# esp32_d1.net
KiCad netlist of a schematic drawn in Altium Designer
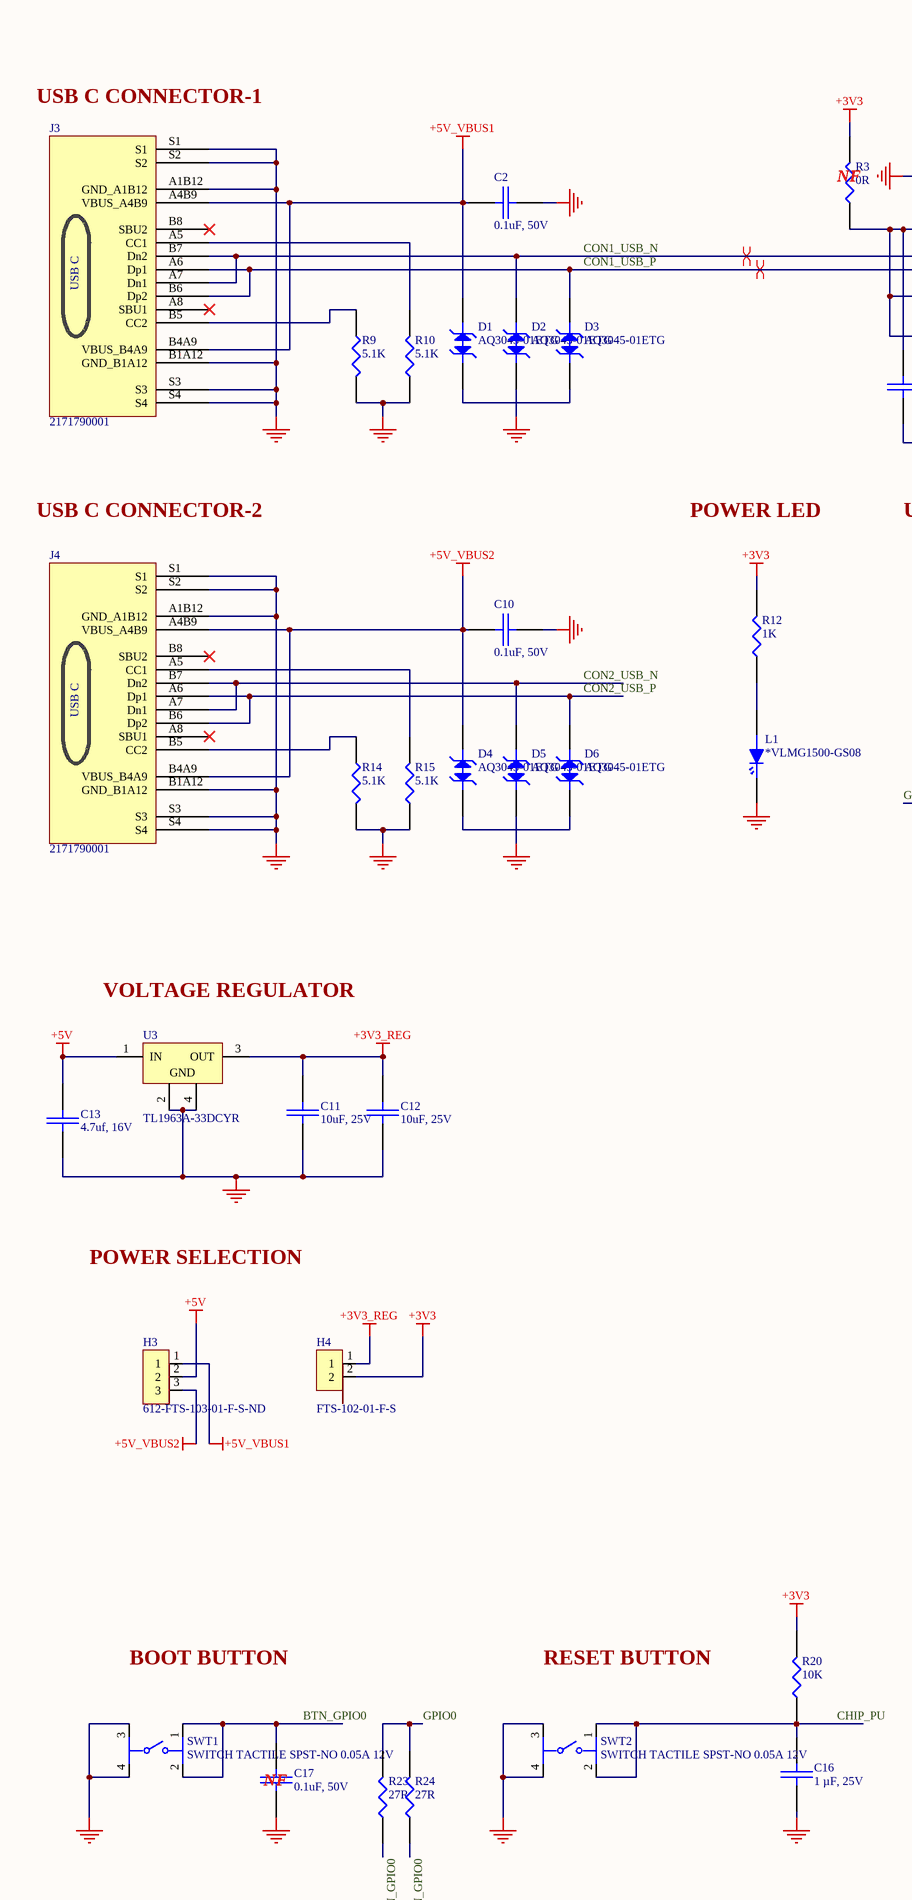
[diagram p0: esp32_d1.SchDoc, left]
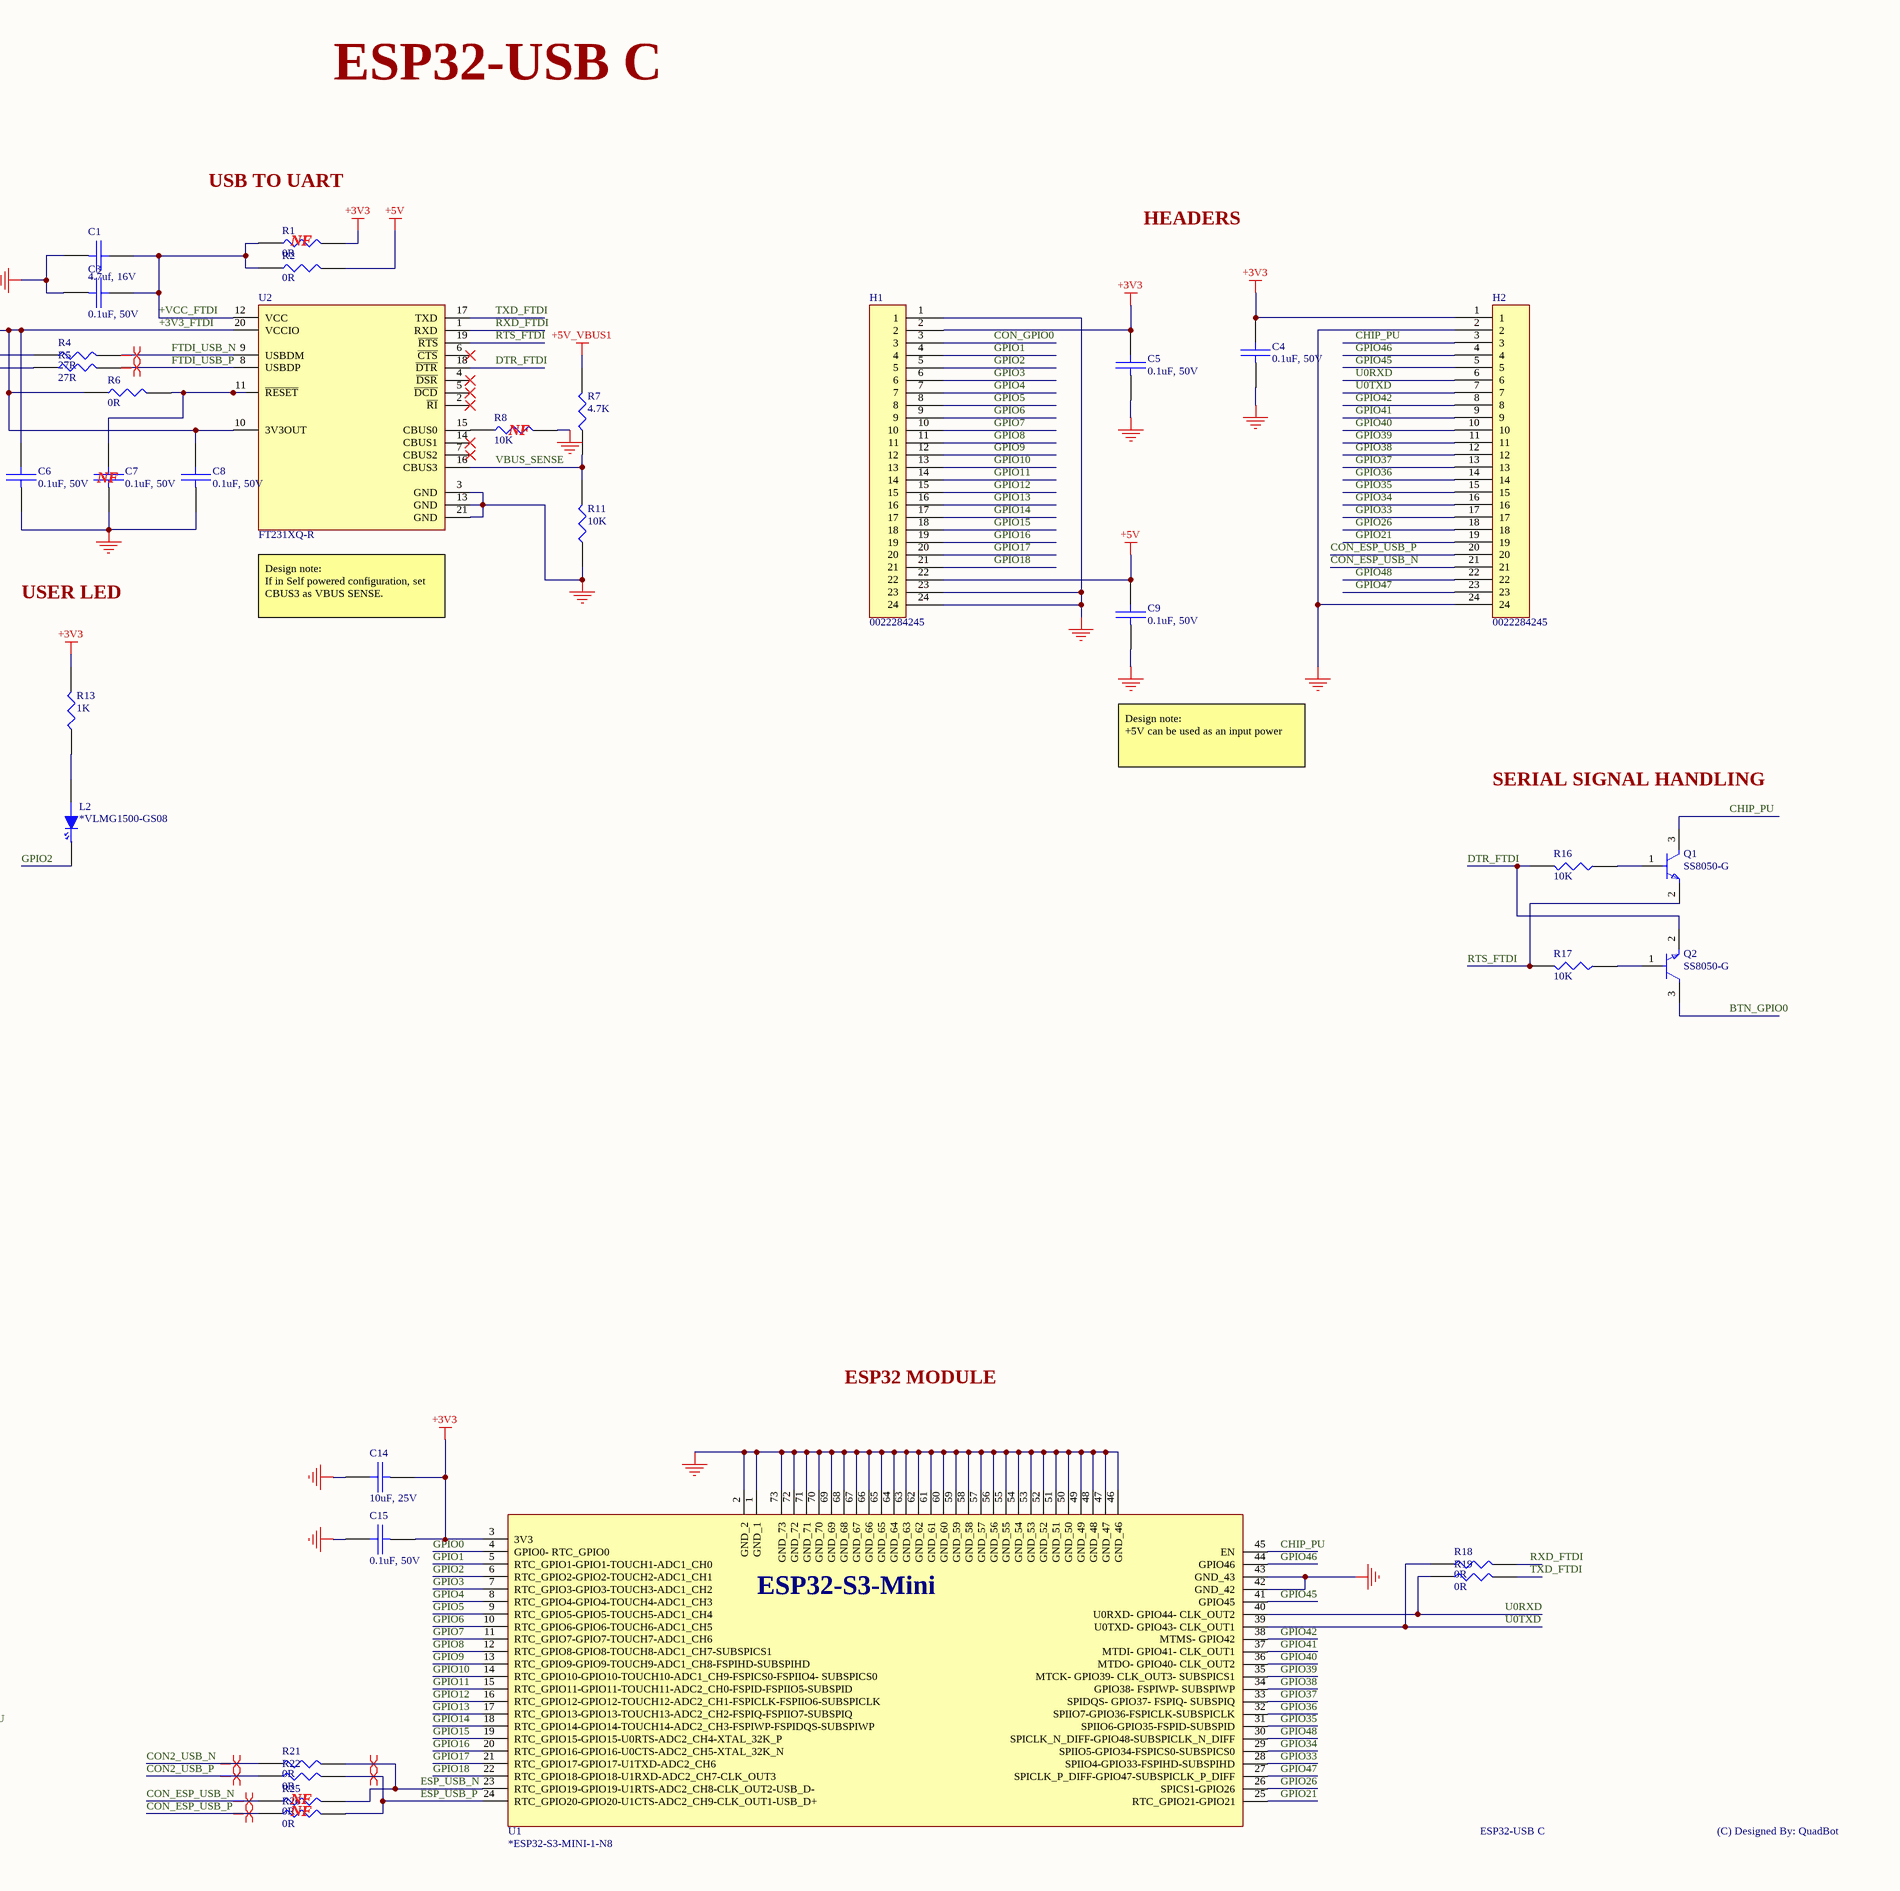
[diagram p1: esp32_d1.SchDoc, right]

(export (version "E")
  (design (tool "Eeschema 10.0.6"))
  (components
    (comp (ref "C1")
      (value "4.7uf, 16V")
      (footprint "CAPC1005X55N")
      (description "CAP CER 4.7UF 16V X5R 0402")
      (fields
        (field (name "MANUFACTURER") "Samsung")
        (field (name "MANUFACTURER PART NUMBER") "CL05A475MO5NUNC")
      )
      (libsource (lib "Esp32_Schlib1") (part "CL05A475MO5NUNC"))
    )
    (comp (ref "C2")
      (value "0.1uF, 50V")
      (footprint "CAPC1005X55N")
      (description "CAP CER 0.1UF 10V X7R 0402")
      (fields
        (field (name "MANUFACTURER") "Samsung")
        (field (name "MANUFACTURER PART NUMBER") "CL05B104KP5NNNC")
      )
      (libsource (lib "Esp32_Schlib1") (part "CL05B104KP5NNNC"))
    )
    (comp (ref "C3")
      (value "0.1uF, 50V")
      (footprint "CAPC1005X55N")
      (description "CAP CER 0.1UF 10V X7R 0402")
      (fields
        (field (name "MANUFACTURER") "Samsung")
        (field (name "MANUFACTURER PART NUMBER") "CL05B104KP5NNNC")
      )
      (libsource (lib "Esp32_Schlib1") (part "CL05B104KP5NNNC"))
    )
    (comp (ref "C4")
      (value "0.1uF, 50V")
      (footprint "CAPC1005X55N")
      (description "CAP CER 0.1UF 10V X7R 0402")
      (fields
        (field (name "MANUFACTURER") "Samsung")
        (field (name "MANUFACTURER PART NUMBER") "CL05B104KP5NNNC")
      )
      (libsource (lib "Esp32_Schlib1") (part "CL05B104KP5NNNC"))
    )
    (comp (ref "C5")
      (value "0.1uF, 50V")
      (footprint "CAPC1005X55N")
      (description "CAP CER 0.1UF 10V X7R 0402")
      (fields
        (field (name "MANUFACTURER") "Samsung")
        (field (name "MANUFACTURER PART NUMBER") "CL05B104KP5NNNC")
      )
      (libsource (lib "Esp32_Schlib1") (part "CL05B104KP5NNNC"))
    )
    (comp (ref "C6")
      (value "0.1uF, 50V")
      (footprint "CAPC1005X55N")
      (description "CAP CER 0.1UF 10V X7R 0402")
      (fields
        (field (name "MANUFACTURER") "Samsung")
        (field (name "MANUFACTURER PART NUMBER") "CL05B104KP5NNNC")
      )
      (libsource (lib "Esp32_Schlib1") (part "CL05B104KP5NNNC"))
    )
    (comp (ref "C7")
      (value "0.1uF, 50V")
      (footprint "CAPC1005X55N")
      (description "CAP CER 0.1UF 10V X7R 0402")
      (fields
        (field (name "MANUFACTURER") "Samsung")
        (field (name "MANUFACTURER PART NUMBER") "CL05B104KP5NNNC")
      )
      (libsource (lib "Esp32_Schlib1") (part "CL05B104KP5NNNC"))
    )
    (comp (ref "C8")
      (value "0.1uF, 50V")
      (footprint "CAPC1005X55N")
      (description "CAP CER 0.1UF 10V X7R 0402")
      (fields
        (field (name "MANUFACTURER") "Samsung")
        (field (name "MANUFACTURER PART NUMBER") "CL05B104KP5NNNC")
      )
      (libsource (lib "Esp32_Schlib1") (part "CL05B104KP5NNNC"))
    )
    (comp (ref "C9")
      (value "0.1uF, 50V")
      (footprint "CAPC1005X55N")
      (description "CAP CER 0.1UF 10V X7R 0402")
      (fields
        (field (name "MANUFACTURER") "Samsung")
        (field (name "MANUFACTURER PART NUMBER") "CL05B104KP5NNNC")
      )
      (libsource (lib "Esp32_Schlib1") (part "CL05B104KP5NNNC"))
    )
    (comp (ref "C10")
      (value "0.1uF, 50V")
      (footprint "CAPC1005X55N")
      (description "CAP CER 0.1UF 10V X7R 0402")
      (fields
        (field (name "MANUFACTURER") "Samsung")
        (field (name "MANUFACTURER PART NUMBER") "CL05B104KP5NNNC")
      )
      (libsource (lib "Esp32_Schlib1") (part "CL05B104KP5NNNC"))
    )
    (comp (ref "C11")
      (value "10uF, 25V")
      (footprint "CAPC1005X55N")
      (description "10V 10uF X5R ±20% 0402 Multilayer Ceramic Capacitors")
      (fields
        (field (name "MANUFACTURER") "Murata")
        (field (name "MANUFACTURER PART NUMBER") "GRM155R60J106ME15D")
      )
      (libsource (lib "Esp32_Schlib1") (part "GRM155R60J106ME15D"))
    )
    (comp (ref "C12")
      (value "10uF, 25V")
      (footprint "CAPC1005X55N")
      (description "10V 10uF X5R ±20% 0402 Multilayer Ceramic Capacitors")
      (fields
        (field (name "MANUFACTURER") "Murata")
        (field (name "MANUFACTURER PART NUMBER") "GRM155R60J106ME15D")
      )
      (libsource (lib "Esp32_Schlib1") (part "GRM155R60J106ME15D"))
    )
    (comp (ref "C13")
      (value "4.7uf, 16V")
      (footprint "CAPC1005X55N")
      (description "CAP CER 4.7UF 16V X5R 0402")
      (fields
        (field (name "MANUFACTURER") "Samsung")
        (field (name "MANUFACTURER PART NUMBER") "CL05A475MO5NUNC")
      )
      (libsource (lib "Esp32_Schlib1") (part "CL05A475MO5NUNC"))
    )
    (comp (ref "C14")
      (value "10uF, 25V")
      (footprint "CAPC1005X55N")
      (description "10V 10uF X5R ±20% 0402 Multilayer Ceramic Capacitors")
      (fields
        (field (name "MANUFACTURER") "Murata")
        (field (name "MANUFACTURER PART NUMBER") "GRM155R60J106ME15D")
      )
      (libsource (lib "Esp32_Schlib1") (part "GRM155R60J106ME15D"))
    )
    (comp (ref "C15")
      (value "0.1uF, 50V")
      (footprint "CAPC1005X55N")
      (description "CAP CER 0.1UF 10V X7R 0402")
      (fields
        (field (name "MANUFACTURER") "Samsung")
        (field (name "MANUFACTURER PART NUMBER") "CL05B104KP5NNNC")
      )
      (libsource (lib "Esp32_Schlib1") (part "CL05B104KP5NNNC"))
    )
    (comp (ref "C16")
      (value "1 µF, 25V")
      (footprint "CAPC1005X55N")
      (description "1 µF ±10% 25V")
      (fields
        (field (name "MANUFACTURER") "Samsung")
        (field (name "MANUFACTURER PART NUMBER") "CL05A105KA5NQNC")
      )
      (libsource (lib "Esp32_Schlib1") (part "CL05A105KA5NQNC"))
    )
    (comp (ref "C17")
      (value "0.1uF, 50V")
      (footprint "CAPC1005X55N")
      (description "CAP CER 0.1UF 10V X7R 0402")
      (fields
        (field (name "MANUFACTURER") "Samsung")
        (field (name "MANUFACTURER PART NUMBER") "CL05B104KP5NNNC")
      )
      (libsource (lib "Esp32_Schlib1") (part "CL05B104KP5NNNC"))
    )
    (comp (ref "D1")
      (value "AQ3045-01ETG")
      (footprint "SOD882")
      (description "Trans Voltage Suppressor Diode, 40W, 5.3V V(RWM), Bidirectional, 1 Element, Silicon, MO-236")
      (fields (field (name "MANUFACTURER") "Littelfuse") (field (name "LCSC PART NUMBER") "C3710326"))
      (libsource (lib "Esp32_Schlib1") (part "AQ3045-01ETG"))
    )
    (comp (ref "D2")
      (value "AQ3045-01ETG")
      (footprint "SOD882")
      (description "Trans Voltage Suppressor Diode, 40W, 5.3V V(RWM), Bidirectional, 1 Element, Silicon, MO-236")
      (fields (field (name "MANUFACTURER") "Littelfuse") (field (name "LCSC PART NUMBER") "C3710326"))
      (libsource (lib "Esp32_Schlib1") (part "AQ3045-01ETG"))
    )
    (comp (ref "D3")
      (value "AQ3045-01ETG")
      (footprint "SOD882")
      (description "Trans Voltage Suppressor Diode, 40W, 5.3V V(RWM), Bidirectional, 1 Element, Silicon, MO-236")
      (fields (field (name "MANUFACTURER") "Littelfuse") (field (name "LCSC PART NUMBER") "C3710326"))
      (libsource (lib "Esp32_Schlib1") (part "AQ3045-01ETG"))
    )
    (comp (ref "D4")
      (value "AQ3045-01ETG")
      (footprint "SOD882")
      (description "Trans Voltage Suppressor Diode, 40W, 5.3V V(RWM), Bidirectional, 1 Element, Silicon, MO-236")
      (fields (field (name "MANUFACTURER") "Littelfuse") (field (name "LCSC PART NUMBER") "C3710326"))
      (libsource (lib "Esp32_Schlib1") (part "AQ3045-01ETG"))
    )
    (comp (ref "D5")
      (value "AQ3045-01ETG")
      (footprint "SOD882")
      (description "Trans Voltage Suppressor Diode, 40W, 5.3V V(RWM), Bidirectional, 1 Element, Silicon, MO-236")
      (fields (field (name "MANUFACTURER") "Littelfuse") (field (name "LCSC PART NUMBER") "C3710326"))
      (libsource (lib "Esp32_Schlib1") (part "AQ3045-01ETG"))
    )
    (comp (ref "D6")
      (value "AQ3045-01ETG")
      (footprint "SOD882")
      (description "Trans Voltage Suppressor Diode, 40W, 5.3V V(RWM), Bidirectional, 1 Element, Silicon, MO-236")
      (fields (field (name "MANUFACTURER") "Littelfuse") (field (name "LCSC PART NUMBER") "C3710326"))
      (libsource (lib "Esp32_Schlib1") (part "AQ3045-01ETG"))
    )
    (comp (ref "H1")
      (value "0022284245")
      (footprint "HDR_1X24_2.54MM")
      (description "CONN HEADER VERT 24POS 2.54MM")
      (fields (field (name "MANUFACTURER") "Molex") (field (name "LCSC PART NUMBER") "C7145888"))
      (libsource (lib "") (part "0022284245_1"))
    )
    (comp (ref "H2")
      (value "0022284245")
      (footprint "HDR_1X24_2.54MM")
      (description "CONN HEADER VERT 24POS 2.54MM")
      (fields (field (name "MANUFACTURER") "Molex") (field (name "LCSC PART NUMBER") "C7145888"))
      (libsource (lib "Esp32_Schlib1") (part "0022284245"))
    )
    (comp (ref "H3")
      (value "612-FTS-103-01-F-S-ND")
      (footprint "HDR_1X3_2.54MM")
      (description "Board Connector, 3 Contact(s), 1 Row(s), Male, Straight, Solder Terminal")
      (fields
        (field (name "MANUFACTURER") "Samtec")
        (field (name "MANUFACTURER PART NUMBER") "FTS-103-01-F-S")
      )
      (libsource (lib "Esp32_Schlib1") (part "FTS-103-01-F-S"))
    )
    (comp (ref "H4")
      (value "FTS-102-01-F-S")
      (footprint "HDR_1X2_2.54MM")
      (fields (field (name "MANUFACTURER") "Samtec") (field (name "LCSC PART NUMBER") "C6045317"))
      (libsource (lib "Esp32_Schlib1") (part "FTS-102-01-F-S"))
    )
    (comp (ref "J3")
      (value "2171790001")
      (footprint "FP-2171790001-MFG")
      (description "CONN RCP USB2.0 TYP C 24P SMD RA")
      (fields (field (name "MANUFACTURER") "Molex") (field (name "MANUFACTURER PART NUMBER") "217179-0001"))
      (libsource (lib "Esp32_Schlib1") (part "217179-0001"))
    )
    (comp (ref "J4")
      (value "2171790001")
      (footprint "FP-2171790001-MFG")
      (description "CONN RCP USB2.0 TYP C 24P SMD RA")
      (fields (field (name "MANUFACTURER") "Molex") (field (name "MANUFACTURER PART NUMBER") "217179-0001"))
      (libsource (lib "Esp32_Schlib1") (part "217179-0001"))
    )
    (comp (ref "L1")
      (value "*VLMG1500-GS08")
      (footprint "LEDC1005X35N")
      (description "LED YLW-GRN 0402 SMD")
      (fields
        (field (name "MANUFACTURER") "Vishay")
        (field (name "MANUFACTURER PART NUMBER") "VLMG1500-GS08")
      )
      (libsource (lib "Esp32_Schlib1") (part "VLMG1500-GS08"))
    )
    (comp (ref "L2")
      (value "*VLMG1500-GS08")
      (footprint "LEDC1005X35N")
      (description "LED YLW-GRN 0402 SMD")
      (fields
        (field (name "MANUFACTURER") "Vishay")
        (field (name "MANUFACTURER PART NUMBER") "VLMG1500-GS08")
      )
      (libsource (lib "Esp32_Schlib1") (part "VLMG1500-GS08"))
    )
    (comp (ref "Q1")
      (value "SS8050-G")
      (footprint "FP-SS8050-G-IPC_B")
      (description "TRANS NPN 25V 1.5A SOT23-3")
      (fields (field (name "MANUFACTURER") "Comchip"))
      (libsource (lib "Esp32_Schlib1") (part "SS8050-G"))
    )
    (comp (ref "Q2")
      (value "SS8050-G")
      (footprint "FP-SS8050-G-IPC_B")
      (description "TRANS NPN 25V 1.5A SOT23-3")
      (fields (field (name "MANUFACTURER") "Comchip"))
      (libsource (lib "Esp32_Schlib1") (part "SS8050-G"))
    )
    (comp (ref "R1")
      (value "0R")
      (footprint "RESC1005X40N")
      (description "RES 0 OHM JUMPER 1/16W 0402")
      (fields
        (field (name "MANUFACTURER") "Yageo")
        (field (name "MANUFACTURER PART NUMBER") "RC0402JR-070RL")
      )
      (libsource (lib "Esp32_Schlib1") (part "RC0402JR-070RL"))
    )
    (comp (ref "R2")
      (value "0R")
      (footprint "RESC1005X40N")
      (description "RES 0 OHM JUMPER 1/16W 0402")
      (fields
        (field (name "MANUFACTURER") "Yageo")
        (field (name "MANUFACTURER PART NUMBER") "RC0402JR-070RL")
      )
      (libsource (lib "Esp32_Schlib1") (part "RC0402JR-070RL"))
    )
    (comp (ref "R3")
      (value "0R")
      (footprint "RESC1005X40N")
      (description "RES 0 OHM JUMPER 1/16W 0402")
      (fields
        (field (name "MANUFACTURER") "Yageo")
        (field (name "MANUFACTURER PART NUMBER") "RC0402JR-070RL")
      )
      (libsource (lib "Esp32_Schlib1") (part "RC0402JR-070RL"))
    )
    (comp (ref "R4")
      (value "27R")
      (footprint "RESC1005X40N")
      (description "RES 27 OHM 5% 1/16W 0402")
      (fields
        (field (name "MANUFACTURER") "Yageo")
        (field (name "MANUFACTURER PART NUMBER") "RC0402JR-0727RL")
      )
      (libsource (lib "Esp32_Schlib1") (part "RC0402JR-0727RL"))
    )
    (comp (ref "R5")
      (value "27R")
      (footprint "RESC1005X40N")
      (description "RES 27 OHM 5% 1/16W 0402")
      (fields
        (field (name "MANUFACTURER") "Yageo")
        (field (name "MANUFACTURER PART NUMBER") "RC0402JR-0727RL")
      )
      (libsource (lib "Esp32_Schlib1") (part "RC0402JR-0727RL"))
    )
    (comp (ref "R6")
      (value "0R")
      (footprint "RESC1005X40N")
      (description "RES 0 OHM JUMPER 1/16W 0402")
      (fields
        (field (name "MANUFACTURER") "Yageo")
        (field (name "MANUFACTURER PART NUMBER") "RC0402JR-070RL")
      )
      (libsource (lib "Esp32_Schlib1") (part "RC0402JR-070RL"))
    )
    (comp (ref "R7")
      (value "4.7K")
      (footprint "RESC1005X40N")
      (description "RES 4.7K OHM 1% 1/16W 0402")
      (fields
        (field (name "MANUFACTURER") "Yageo")
        (field (name "MANUFACTURER PART NUMBER") "RC0402FR-074K7L")
      )
      (libsource (lib "Esp32_Schlib1") (part "RC0402FR-074K7L"))
    )
    (comp (ref "R8")
      (value "10K")
      (footprint "RESC1005X40N")
      (description "10 kOhms ±1% 0.063W, 1/16W")
      (fields
        (field (name "MANUFACTURER") "Samsung")
        (field (name "MANUFACTURER PART NUMBER") "RC1005F103CS")
      )
      (libsource (lib "Esp32_Schlib1") (part "RC1005F103CS"))
    )
    (comp (ref "R9")
      (value "5.1K")
      (footprint "RESC1005X40N")
      (description "RES 5.1K OHM 1% 1/16W 0402")
      (fields
        (field (name "MANUFACTURER") "Yageo")
        (field (name "MANUFACTURER PART NUMBER") "RC0402FR-075K1L")
      )
      (libsource (lib "Esp32_Schlib1") (part "RC0402FR-075K1L"))
    )
    (comp (ref "R10")
      (value "5.1K")
      (footprint "RESC1005X40N")
      (description "RES 5.1K OHM 1% 1/16W 0402")
      (fields
        (field (name "MANUFACTURER") "Yageo")
        (field (name "MANUFACTURER PART NUMBER") "RC0402FR-075K1L")
      )
      (libsource (lib "Esp32_Schlib1") (part "RC0402FR-075K1L"))
    )
    (comp (ref "R11")
      (value "10K")
      (footprint "RESC1005X40N")
      (description "10 kOhms ±1% 0.063W, 1/16W")
      (fields
        (field (name "MANUFACTURER") "Samsung")
        (field (name "MANUFACTURER PART NUMBER") "RC1005F103CS")
      )
      (libsource (lib "Esp32_Schlib1") (part "RC1005F103CS"))
    )
    (comp (ref "R12")
      (value "1K")
      (footprint "RESC1005X40N")
      (description "RES 1K OHM 1% 1/16W 0402")
      (fields
        (field (name "MANUFACTURER") "Yageo")
        (field (name "MANUFACTURER PART NUMBER") "RC0402FR-071KL")
      )
      (libsource (lib "Esp32_Schlib1") (part "RC0402FR-071KL"))
    )
    (comp (ref "R13")
      (value "1K")
      (footprint "RESC1005X40N")
      (description "RES 1K OHM 1% 1/16W 0402")
      (fields
        (field (name "MANUFACTURER") "Yageo")
        (field (name "MANUFACTURER PART NUMBER") "RC0402FR-071KL")
      )
      (libsource (lib "Esp32_Schlib1") (part "RC0402FR-071KL"))
    )
    (comp (ref "R14")
      (value "5.1K")
      (footprint "RESC1005X40N")
      (description "RES 5.1K OHM 1% 1/16W 0402")
      (fields
        (field (name "MANUFACTURER") "Yageo")
        (field (name "MANUFACTURER PART NUMBER") "RC0402FR-075K1L")
      )
      (libsource (lib "Esp32_Schlib1") (part "RC0402FR-075K1L"))
    )
    (comp (ref "R15")
      (value "5.1K")
      (footprint "RESC1005X40N")
      (description "RES 5.1K OHM 1% 1/16W 0402")
      (fields
        (field (name "MANUFACTURER") "Yageo")
        (field (name "MANUFACTURER PART NUMBER") "RC0402FR-075K1L")
      )
      (libsource (lib "Esp32_Schlib1") (part "RC0402FR-075K1L"))
    )
    (comp (ref "R16")
      (value "10K")
      (footprint "RESC1005X40N")
      (description "10 kOhms ±1% 0.063W, 1/16W")
      (fields
        (field (name "MANUFACTURER") "Samsung")
        (field (name "MANUFACTURER PART NUMBER") "RC1005F103CS")
      )
      (libsource (lib "Esp32_Schlib1") (part "RC1005F103CS"))
    )
    (comp (ref "R17")
      (value "10K")
      (footprint "RESC1005X40N")
      (description "10 kOhms ±1% 0.063W, 1/16W")
      (fields
        (field (name "MANUFACTURER") "Samsung")
        (field (name "MANUFACTURER PART NUMBER") "RC1005F103CS")
      )
      (libsource (lib "Esp32_Schlib1") (part "RC1005F103CS"))
    )
    (comp (ref "R18")
      (value "0R")
      (footprint "RESC1005X40N")
      (description "RES 0 OHM JUMPER 1/16W 0402")
      (fields
        (field (name "MANUFACTURER") "Yageo")
        (field (name "MANUFACTURER PART NUMBER") "RC0402JR-070RL")
      )
      (libsource (lib "Esp32_Schlib1") (part "RC0402JR-070RL"))
    )
    (comp (ref "R19")
      (value "0R")
      (footprint "RESC1005X40N")
      (description "RES 0 OHM JUMPER 1/16W 0402")
      (fields
        (field (name "MANUFACTURER") "Yageo")
        (field (name "MANUFACTURER PART NUMBER") "RC0402JR-070RL")
      )
      (libsource (lib "Esp32_Schlib1") (part "RC0402JR-070RL"))
    )
    (comp (ref "R20")
      (value "10K")
      (footprint "RESC1005X40N")
      (description "10 kOhms ±1% 0.063W, 1/16W")
      (fields
        (field (name "MANUFACTURER") "Samsung")
        (field (name "MANUFACTURER PART NUMBER") "RC1005F103CS")
      )
      (libsource (lib "Esp32_Schlib1") (part "RC1005F103CS"))
    )
    (comp (ref "R21")
      (value "0R")
      (footprint "RESC1005X40N")
      (description "RES 0 OHM JUMPER 1/16W 0402")
      (fields
        (field (name "MANUFACTURER") "Yageo")
        (field (name "MANUFACTURER PART NUMBER") "RC0402JR-070RL")
      )
      (libsource (lib "Esp32_Schlib1") (part "RC0402JR-070RL"))
    )
    (comp (ref "R22")
      (value "0R")
      (footprint "RESC1005X40N")
      (description "RES 0 OHM JUMPER 1/16W 0402")
      (fields
        (field (name "MANUFACTURER") "Yageo")
        (field (name "MANUFACTURER PART NUMBER") "RC0402JR-070RL")
      )
      (libsource (lib "Esp32_Schlib1") (part "RC0402JR-070RL"))
    )
    (comp (ref "R23")
      (value "27R")
      (footprint "RESC1005X40N")
      (description "RES 27 OHM 5% 1/16W 0402")
      (fields
        (field (name "MANUFACTURER") "Yageo")
        (field (name "MANUFACTURER PART NUMBER") "RC0402JR-0727RL")
      )
      (libsource (lib "Esp32_Schlib1") (part "RC0402JR-0727RL"))
    )
    (comp (ref "R24")
      (value "27R")
      (footprint "RESC1005X40N")
      (description "RES 27 OHM 5% 1/16W 0402")
      (fields
        (field (name "MANUFACTURER") "Yageo")
        (field (name "MANUFACTURER PART NUMBER") "RC0402JR-0727RL")
      )
      (libsource (lib "Esp32_Schlib1") (part "RC0402JR-0727RL"))
    )
    (comp (ref "R25")
      (value "0R")
      (footprint "RESC1005X40N")
      (description "RES 0 OHM JUMPER 1/16W 0402")
      (fields
        (field (name "MANUFACTURER") "Yageo")
        (field (name "MANUFACTURER PART NUMBER") "RC0402JR-070RL")
      )
      (libsource (lib "Esp32_Schlib1") (part "RC0402JR-070RL"))
    )
    (comp (ref "R26")
      (value "0R")
      (footprint "RESC1005X40N")
      (description "RES 0 OHM JUMPER 1/16W 0402")
      (fields
        (field (name "MANUFACTURER") "Yageo")
        (field (name "MANUFACTURER PART NUMBER") "RC0402JR-070RL")
      )
      (libsource (lib "Esp32_Schlib1") (part "RC0402JR-070RL"))
    )
    (comp (ref "SWT1")
      (value "SWITCH TACTILE SPST-NO 0.05A 12V")
      (footprint "FP-PTS645SH50SMTR92LFS-MFG")
      (fields
        (field (name "MANUFACTURER") "ITT C&K")
        (field (name "MANUFACTURER PART NUMBER") "PTS645SH50SMTR92LFS")
        (field (name "LCSC PART NUMBER") "C221869")
      )
      (libsource (lib "Esp32_Schlib1") (part "PTS645SH50SMTR92LFS"))
    )
    (comp (ref "SWT2")
      (value "SWITCH TACTILE SPST-NO 0.05A 12V")
      (footprint "FP-PTS645SH50SMTR92LFS-MFG")
      (fields
        (field (name "MANUFACTURER") "ITT C&K")
        (field (name "MANUFACTURER PART NUMBER") "PTS645SH50SMTR92LFS")
        (field (name "LCSC PART NUMBER") "C221869")
      )
      (libsource (lib "Esp32_Schlib1") (part "PTS645SH50SMTR92LFS"))
    )
    (comp (ref "U1")
      (value "*ESP32-S3-MINI-1-N8")
      (footprint "XCVR_ESP32-S3-MINI-1-N8")
      (description "SMD module, ESP32-S3FN8, 8 MB SPI flash, PCB antenna")
      (fields
        (field (name "MANUFACTURER") "Espressif Systems")
        (field (name "MANUFACTURER PART NUMBER") "ESP32-S3-MINI-1-N8")
      )
      (libsource (lib "Esp32_Schlib1") (part "ESP32-S3-MINI-1-N8"))
    )
    (comp (ref "U2")
      (value "FT231XQ-R")
      (footprint "FP-QFN-20-IPC_B")
      (description "IC USB SERIAL FULL UART 20QFN")
      (fields (field (name "MANUFACTURER") "FTDI") (field (name "LCSC PART NUMBER") "C132159"))
      (libsource (lib "Esp32_Schlib1") (part "FT231XQ-R"))
    )
    (comp (ref "U3")
      (value "TL1963A-33DCYR")
      (footprint "DCY0004A_N")
      (description "IC REG LINEAR 3.3V 1.5A SOT223-4")
      (fields (field (name "MANUFACTURER") "Texas Instruments") (field (name "LCSC PART NUMBER") "C181262"))
      (libsource (lib "Esp32_Schlib1") (part "TL1963A-33DCYR"))
    )
  )
  (nets
    (net (code "1") (name "+3V3") (class "Default")
      (node (ref "C14") (pin "2") (pinfunction "2_2") (pintype "passive"))
      (node (ref "C15") (pin "2") (pinfunction "2_2") (pintype "passive"))
      (node (ref "C4") (pin "1") (pinfunction "1_1") (pintype "passive"))
      (node (ref "C5") (pin "1") (pinfunction "1_1") (pintype "passive"))
      (node (ref "H1") (pin "2") (pinfunction "2_2") (pintype "passive"))
      (node (ref "H2") (pin "1") (pinfunction "1_1") (pintype "passive"))
      (node (ref "H4") (pin "2") (pinfunction "2_2") (pintype "passive"))
      (node (ref "R1") (pin "2") (pinfunction "2_2") (pintype "passive"))
      (node (ref "R12") (pin "2") (pinfunction "2_2") (pintype "passive"))
      (node (ref "R13") (pin "2") (pinfunction "2_2") (pintype "passive"))
      (node (ref "R20") (pin "2") (pinfunction "2_2") (pintype "passive"))
      (node (ref "R3") (pin "2") (pinfunction "2_2") (pintype "passive"))
      (node (ref "U1") (pin "3") (pinfunction "3V3_3") (pintype "passive"))
    )
    (net (code "2") (name "+3V3_REG") (class "Default")
      (node (ref "C11") (pin "2") (pinfunction "2_2") (pintype "passive"))
      (node (ref "C12") (pin "2") (pinfunction "2_2") (pintype "passive"))
      (node (ref "H4") (pin "1") (pinfunction "1_1") (pintype "passive"))
      (node (ref "U3") (pin "3") (pinfunction "OUT_3") (pintype "power_in"))
    )
    (net (code "3") (name "+5V") (class "Default")
      (node (ref "C13") (pin "1") (pinfunction "1_1") (pintype "passive"))
      (node (ref "C9") (pin "1") (pinfunction "1_1") (pintype "passive"))
      (node (ref "H1") (pin "22") (pinfunction "22_22") (pintype "passive"))
      (node (ref "H3") (pin "2") (pinfunction "2_2") (pintype "passive"))
      (node (ref "R2") (pin "2") (pinfunction "2_2") (pintype "passive"))
      (node (ref "U3") (pin "1") (pinfunction "IN_1") (pintype "power_in"))
    )
    (net (code "4") (name "+5V_VBUS1") (class "Default")
      (node (ref "C2") (pin "2") (pinfunction "2_2") (pintype "passive"))
      (node (ref "D1") (pin "1") (pinfunction "1_1") (pintype "passive"))
      (node (ref "H3") (pin "1") (pinfunction "1_1") (pintype "passive"))
      (node (ref "J3") (pin "A4B9") (pinfunction "VBUS_A4B9_A4B9") (pintype "passive"))
      (node (ref "J3") (pin "B4A9") (pinfunction "VBUS_B4A9_B4A9") (pintype "passive"))
      (node (ref "R7") (pin "2") (pinfunction "2_2") (pintype "passive"))
    )
    (net (code "5") (name "+5V_VBUS2") (class "Default")
      (node (ref "C10") (pin "2") (pinfunction "2_2") (pintype "passive"))
      (node (ref "D4") (pin "1") (pinfunction "1_1") (pintype "passive"))
      (node (ref "H3") (pin "3") (pinfunction "3_3") (pintype "passive"))
      (node (ref "J4") (pin "A4B9") (pinfunction "VBUS_A4B9_A4B9") (pintype "passive"))
      (node (ref "J4") (pin "B4A9") (pinfunction "VBUS_B4A9_B4A9") (pintype "passive"))
    )
    (net (code "6") (name "/+3V3_FTDI") (class "Default")
      (node (ref "C6") (pin "1") (pinfunction "1_1") (pintype "passive"))
      (node (ref "C8") (pin "1") (pinfunction "1_1") (pintype "passive"))
      (node (ref "R3") (pin "1") (pinfunction "1_1") (pintype "passive"))
      (node (ref "R6") (pin "1") (pinfunction "1_1") (pintype "passive"))
      (node (ref "U2") (pin "10") (pinfunction "3V3OUT_10") (pintype "passive"))
      (node (ref "U2") (pin "20") (pinfunction "VCCIO_20") (pintype "passive"))
    )
    (net (code "7") (name "/+VCC_FTDI") (class "Default")
      (node (ref "C1") (pin "1") (pinfunction "1_1") (pintype "passive"))
      (node (ref "C3") (pin "1") (pinfunction "1_1") (pintype "passive"))
      (node (ref "R1") (pin "1") (pinfunction "1_1") (pintype "passive"))
      (node (ref "R2") (pin "1") (pinfunction "1_1") (pintype "passive"))
      (node (ref "U2") (pin "12") (pinfunction "VCC_12") (pintype "passive"))
    )
    (net (code "8") (name "/BTN_GPIO0") (class "Default")
      (node (ref "C17") (pin "2") (pinfunction "2_2") (pintype "passive"))
      (node (ref "Q2") (pin "3") (pinfunction "C_3") (pintype "passive"))
      (node (ref "R24") (pin "1") (pinfunction "1_1") (pintype "passive"))
      (node (ref "SWT1") (pin "1") (pinfunction "1_1") (pintype "passive"))
      (node (ref "SWT1") (pin "2") (pinfunction "2_2") (pintype "passive"))
    )
    (net (code "9") (name "/CHIP_PU") (class "Default")
      (node (ref "C16") (pin "1") (pinfunction "1_1") (pintype "passive"))
      (node (ref "H2") (pin "3") (pinfunction "3_3") (pintype "passive"))
      (node (ref "Q1") (pin "3") (pinfunction "C_3") (pintype "passive"))
      (node (ref "R20") (pin "1") (pinfunction "1_1") (pintype "passive"))
      (node (ref "SWT2") (pin "1") (pinfunction "1_1") (pintype "passive"))
      (node (ref "SWT2") (pin "2") (pinfunction "2_2") (pintype "passive"))
      (node (ref "U1") (pin "45") (pinfunction "EN_45") (pintype "passive"))
    )
    (net (code "10") (name "/CON1_USB_N") (class "Default")
      (node (ref "D2") (pin "1") (pinfunction "1_1") (pintype "passive"))
      (node (ref "J3") (pin "A7") (pinfunction "Dn1_A7") (pintype "passive"))
      (node (ref "J3") (pin "B7") (pinfunction "Dn2_B7") (pintype "passive"))
      (node (ref "R4") (pin "1") (pinfunction "1_1") (pintype "passive"))
    )
    (net (code "11") (name "/CON1_USB_P") (class "Default")
      (node (ref "D3") (pin "1") (pinfunction "1_1") (pintype "passive"))
      (node (ref "J3") (pin "A6") (pinfunction "Dp1_A6") (pintype "passive"))
      (node (ref "J3") (pin "B6") (pinfunction "Dp2_B6") (pintype "passive"))
      (node (ref "R5") (pin "1") (pinfunction "1_1") (pintype "passive"))
    )
    (net (code "12") (name "/CON2_USB_N") (class "Default")
      (node (ref "D5") (pin "1") (pinfunction "1_1") (pintype "passive"))
      (node (ref "J4") (pin "A7") (pinfunction "Dn1_A7") (pintype "passive"))
      (node (ref "J4") (pin "B7") (pinfunction "Dn2_B7") (pintype "passive"))
      (node (ref "R21") (pin "1") (pinfunction "1_1") (pintype "passive"))
    )
    (net (code "13") (name "/CON2_USB_P") (class "Default")
      (node (ref "D6") (pin "1") (pinfunction "1_1") (pintype "passive"))
      (node (ref "J4") (pin "A6") (pinfunction "Dp1_A6") (pintype "passive"))
      (node (ref "J4") (pin "B6") (pinfunction "Dp2_B6") (pintype "passive"))
      (node (ref "R22") (pin "1") (pinfunction "1_1") (pintype "passive"))
    )
    (net (code "14") (name "/CON_ESP_USB_N") (class "Default")
      (node (ref "H2") (pin "21") (pinfunction "21_21") (pintype "passive"))
      (node (ref "R25") (pin "1") (pinfunction "1_1") (pintype "passive"))
    )
    (net (code "15") (name "/CON_ESP_USB_P") (class "Default")
      (node (ref "H2") (pin "20") (pinfunction "20_20") (pintype "passive"))
      (node (ref "R26") (pin "1") (pinfunction "1_1") (pintype "passive"))
    )
    (net (code "16") (name "/CON_GPIO0") (class "Default")
      (node (ref "H1") (pin "3") (pinfunction "3_3") (pintype "passive"))
      (node (ref "R23") (pin "1") (pinfunction "1_1") (pintype "passive"))
    )
    (net (code "17") (name "/DTR_FTDI") (class "Default")
      (node (ref "Q2") (pin "2") (pinfunction "E_2") (pintype "passive"))
      (node (ref "R16") (pin "2") (pinfunction "2_2") (pintype "passive"))
      (node (ref "U2") (pin "18") (pinfunction "~{DTR}_18") (pintype "passive"))
    )
    (net (code "18") (name "/ESP_USB_N") (class "Default")
      (node (ref "R21") (pin "2") (pinfunction "2_2") (pintype "passive"))
      (node (ref "R25") (pin "2") (pinfunction "2_2") (pintype "passive"))
      (node (ref "U1") (pin "23") (pinfunction "RTC_GPIO19-GPIO19-U1RTS-ADC2_CH8-CLK_OUT2-USB_D-_23") (pintype "passive"))
    )
    (net (code "19") (name "/ESP_USB_P") (class "Default")
      (node (ref "R22") (pin "2") (pinfunction "2_2") (pintype "passive"))
      (node (ref "R26") (pin "2") (pinfunction "2_2") (pintype "passive"))
      (node (ref "U1") (pin "24") (pinfunction "RTC_GPIO20-GPIO20-U1CTS-ADC2_CH9-CLK_OUT1-USB_D+_24") (pintype "passive"))
    )
    (net (code "20") (name "/FTDI_USB_N") (class "Default")
      (node (ref "R4") (pin "2") (pinfunction "2_2") (pintype "passive"))
      (node (ref "U2") (pin "9") (pinfunction "USBDM_9") (pintype "passive"))
    )
    (net (code "21") (name "/FTDI_USB_P") (class "Default")
      (node (ref "R5") (pin "2") (pinfunction "2_2") (pintype "passive"))
      (node (ref "U2") (pin "8") (pinfunction "USBDP_8") (pintype "passive"))
    )
    (net (code "22") (name "/GPIO0") (class "Default")
      (node (ref "R23") (pin "2") (pinfunction "2_2") (pintype "passive"))
      (node (ref "R24") (pin "2") (pinfunction "2_2") (pintype "passive"))
      (node (ref "U1") (pin "4") (pinfunction "GPIO0-_RTC_GPIO0_4") (pintype "passive"))
    )
    (net (code "23") (name "/GPIO1") (class "Default")
      (node (ref "H1") (pin "4") (pinfunction "4_4") (pintype "passive"))
      (node (ref "U1") (pin "5") (pinfunction "RTC_GPIO1-GPIO1-TOUCH1-ADC1_CH0_5") (pintype "passive"))
    )
    (net (code "24") (name "/GPIO2") (class "Default")
      (node (ref "H1") (pin "5") (pinfunction "5_5") (pintype "passive"))
      (node (ref "L2") (pin "1") (pinfunction "1_1") (pintype "passive"))
      (node (ref "U1") (pin "6") (pinfunction "RTC_GPIO2-GPIO2-TOUCH2-ADC1_CH1_6") (pintype "passive"))
    )
    (net (code "25") (name "/GPIO3") (class "Default")
      (node (ref "H1") (pin "6") (pinfunction "6_6") (pintype "passive"))
      (node (ref "U1") (pin "7") (pinfunction "RTC_GPIO3-GPIO3-TOUCH3-ADC1_CH2_7") (pintype "passive"))
    )
    (net (code "26") (name "/GPIO4") (class "Default")
      (node (ref "H1") (pin "7") (pinfunction "7_7") (pintype "passive"))
      (node (ref "U1") (pin "8") (pinfunction "RTC_GPIO4-GPIO4-TOUCH4-ADC1_CH3_8") (pintype "passive"))
    )
    (net (code "27") (name "/GPIO5") (class "Default")
      (node (ref "H1") (pin "8") (pinfunction "8_8") (pintype "passive"))
      (node (ref "U1") (pin "9") (pinfunction "RTC_GPIO5-GPIO5-TOUCH5-ADC1_CH4_9") (pintype "passive"))
    )
    (net (code "28") (name "/GPIO6") (class "Default")
      (node (ref "H1") (pin "9") (pinfunction "9_9") (pintype "passive"))
      (node (ref "U1") (pin "10") (pinfunction "RTC_GPIO6-GPIO6-TOUCH6-ADC1_CH5_10") (pintype "passive"))
    )
    (net (code "29") (name "/GPIO7") (class "Default")
      (node (ref "H1") (pin "10") (pinfunction "10_10") (pintype "passive"))
      (node (ref "U1") (pin "11") (pinfunction "RTC_GPIO7-GPIO7-TOUCH7-ADC1_CH6_11") (pintype "passive"))
    )
    (net (code "30") (name "/GPIO8") (class "Default")
      (node (ref "H1") (pin "11") (pinfunction "11_11") (pintype "passive"))
      (node (ref "U1") (pin "12") (pinfunction "RTC_GPIO8-GPIO8-TOUCH8-ADC1_CH7-SUBSPICS1_12") (pintype "passive"))
    )
    (net (code "31") (name "/GPIO9") (class "Default")
      (node (ref "H1") (pin "12") (pinfunction "12_12") (pintype "passive"))
      (node (ref "U1") (pin "13") (pinfunction "RTC_GPIO9-GPIO9-TOUCH9-ADC1_CH8-FSPIHD-SUBSPIHD_13") (pintype "passive"))
    )
    (net (code "32") (name "/GPIO10") (class "Default")
      (node (ref "H1") (pin "13") (pinfunction "13_13") (pintype "passive"))
      (node (ref "U1") (pin "14") (pinfunction "RTC_GPIO10-GPIO10-TOUCH10-ADC1_CH9-FSPICS0-FSPIIO4-_SUBSPICS0_14") (pintype "passive"))
    )
    (net (code "33") (name "/GPIO11") (class "Default")
      (node (ref "H1") (pin "14") (pinfunction "14_14") (pintype "passive"))
      (node (ref "U1") (pin "15") (pinfunction "RTC_GPIO11-GPIO11-TOUCH11-ADC2_CH0-FSPID-FSPIIO5-SUBSPID_15") (pintype "passive"))
    )
    (net (code "34") (name "/GPIO12") (class "Default")
      (node (ref "H1") (pin "15") (pinfunction "15_15") (pintype "passive"))
      (node (ref "U1") (pin "16") (pinfunction "RTC_GPIO12-GPIO12-TOUCH12-ADC2_CH1-FSPICLK-FSPIIO6-SUBSPICLK_16") (pintype "passive"))
    )
    (net (code "35") (name "/GPIO13") (class "Default")
      (node (ref "H1") (pin "16") (pinfunction "16_16") (pintype "passive"))
      (node (ref "U1") (pin "17") (pinfunction "RTC_GPIO13-GPIO13-TOUCH13-ADC2_CH2-FSPIQ-FSPIIO7-SUBSPIQ_17") (pintype "passive"))
    )
    (net (code "36") (name "/GPIO14") (class "Default")
      (node (ref "H1") (pin "17") (pinfunction "17_17") (pintype "passive"))
      (node (ref "U1") (pin "18") (pinfunction "RTC_GPIO14-GPIO14-TOUCH14-ADC2_CH3-FSPIWP-FSPIDQS-SUBSPIWP_18") (pintype "passive"))
    )
    (net (code "37") (name "/GPIO15") (class "Default")
      (node (ref "H1") (pin "18") (pinfunction "18_18") (pintype "passive"))
      (node (ref "U1") (pin "19") (pinfunction "RTC_GPIO15-GPIO15-U0RTS-ADC2_CH4-XTAL_32K_P_19") (pintype "passive"))
    )
    (net (code "38") (name "/GPIO16") (class "Default")
      (node (ref "H1") (pin "19") (pinfunction "19_19") (pintype "passive"))
      (node (ref "U1") (pin "20") (pinfunction "RTC_GPIO16-GPIO16-U0CTS-ADC2_CH5-XTAL_32K_N_20") (pintype "passive"))
    )
    (net (code "39") (name "/GPIO17") (class "Default")
      (node (ref "H1") (pin "20") (pinfunction "20_20") (pintype "passive"))
      (node (ref "U1") (pin "21") (pinfunction "RTC_GPIO17-GPIO17-U1TXD-ADC2_CH6_21") (pintype "passive"))
    )
    (net (code "40") (name "/GPIO18") (class "Default")
      (node (ref "H1") (pin "21") (pinfunction "21_21") (pintype "passive"))
      (node (ref "U1") (pin "22") (pinfunction "RTC_GPIO18-GPIO18-U1RXD-ADC2_CH7-CLK_OUT3_22") (pintype "passive"))
    )
    (net (code "41") (name "/GPIO21") (class "Default")
      (node (ref "H2") (pin "19") (pinfunction "19_19") (pintype "passive"))
      (node (ref "U1") (pin "25") (pinfunction "RTC_GPIO21-GPIO21_25") (pintype "passive"))
    )
    (net (code "42") (name "/GPIO26") (class "Default")
      (node (ref "H2") (pin "18") (pinfunction "18_18") (pintype "passive"))
      (node (ref "U1") (pin "26") (pinfunction "SPICS1-GPIO26_26") (pintype "passive"))
    )
    (net (code "43") (name "/GPIO33") (class "Default")
      (node (ref "H2") (pin "17") (pinfunction "17_17") (pintype "passive"))
      (node (ref "U1") (pin "28") (pinfunction "SPIIO4-GPIO33-FSPIHD-SUBSPIHD_28") (pintype "passive"))
    )
    (net (code "44") (name "/GPIO34") (class "Default")
      (node (ref "H2") (pin "16") (pinfunction "16_16") (pintype "passive"))
      (node (ref "U1") (pin "29") (pinfunction "SPIIO5-GPIO34-FSPICS0-SUBSPICS0_29") (pintype "passive"))
    )
    (net (code "45") (name "/GPIO35") (class "Default")
      (node (ref "H2") (pin "15") (pinfunction "15_15") (pintype "passive"))
      (node (ref "U1") (pin "31") (pinfunction "SPIIO6-GPIO35-FSPID-SUBSPID_31") (pintype "passive"))
    )
    (net (code "46") (name "/GPIO36") (class "Default")
      (node (ref "H2") (pin "14") (pinfunction "14_14") (pintype "passive"))
      (node (ref "U1") (pin "32") (pinfunction "SPIIO7-GPIO36-FSPICLK-SUBSPICLK_32") (pintype "passive"))
    )
    (net (code "47") (name "/GPIO37") (class "Default")
      (node (ref "H2") (pin "13") (pinfunction "13_13") (pintype "passive"))
      (node (ref "U1") (pin "33") (pinfunction "SPIDQS-_GPIO37-_FSPIQ-_SUBSPIQ_33") (pintype "passive"))
    )
    (net (code "48") (name "/GPIO38") (class "Default")
      (node (ref "H2") (pin "12") (pinfunction "12_12") (pintype "passive"))
      (node (ref "U1") (pin "34") (pinfunction "GPIO38-_FSPIWP-_SUBSPIWP_34") (pintype "passive"))
    )
    (net (code "49") (name "/GPIO39") (class "Default")
      (node (ref "H2") (pin "11") (pinfunction "11_11") (pintype "passive"))
      (node (ref "U1") (pin "35") (pinfunction "MTCK-_GPIO39-_CLK_OUT3-_SUBSPICS1_35") (pintype "passive"))
    )
    (net (code "50") (name "/GPIO40") (class "Default")
      (node (ref "H2") (pin "10") (pinfunction "10_10") (pintype "passive"))
      (node (ref "U1") (pin "36") (pinfunction "MTDO-_GPIO40-_CLK_OUT2_36") (pintype "passive"))
    )
    (net (code "51") (name "/GPIO41") (class "Default")
      (node (ref "H2") (pin "9") (pinfunction "9_9") (pintype "passive"))
      (node (ref "U1") (pin "37") (pinfunction "MTDI-_GPIO41-_CLK_OUT1_37") (pintype "passive"))
    )
    (net (code "52") (name "/GPIO42") (class "Default")
      (node (ref "H2") (pin "8") (pinfunction "8_8") (pintype "passive"))
      (node (ref "U1") (pin "38") (pinfunction "MTMS-_GPIO42_38") (pintype "passive"))
    )
    (net (code "53") (name "/GPIO45") (class "Default")
      (node (ref "H2") (pin "5") (pinfunction "5_5") (pintype "passive"))
      (node (ref "U1") (pin "41") (pinfunction "GPIO45_41") (pintype "passive"))
    )
    (net (code "54") (name "/GPIO46") (class "Default")
      (node (ref "H2") (pin "4") (pinfunction "4_4") (pintype "passive"))
      (node (ref "U1") (pin "44") (pinfunction "GPIO46_44") (pintype "passive"))
    )
    (net (code "55") (name "/GPIO47") (class "Default")
      (node (ref "H2") (pin "23") (pinfunction "23_23") (pintype "passive"))
      (node (ref "U1") (pin "27") (pinfunction "SPICLK_P_DIFF-GPIO47-SUBSPICLK_P_DIFF_27") (pintype "passive"))
    )
    (net (code "56") (name "/GPIO48") (class "Default")
      (node (ref "H2") (pin "22") (pinfunction "22_22") (pintype "passive"))
      (node (ref "U1") (pin "30") (pinfunction "SPICLK_N_DIFF-GPIO48-SUBSPICLK_N_DIFF_30") (pintype "passive"))
    )
    (net (code "57") (name "/RTS_FTDI") (class "Default")
      (node (ref "Q1") (pin "2") (pinfunction "E_2") (pintype "passive"))
      (node (ref "R17") (pin "2") (pinfunction "2_2") (pintype "passive"))
      (node (ref "U2") (pin "19") (pinfunction "~{RTS}_19") (pintype "passive"))
    )
    (net (code "58") (name "/RXD_FTDI") (class "Default")
      (node (ref "R18") (pin "2") (pinfunction "2_2") (pintype "passive"))
      (node (ref "U2") (pin "1") (pinfunction "RXD_1") (pintype "passive"))
    )
    (net (code "59") (name "/TXD_FTDI") (class "Default")
      (node (ref "R19") (pin "2") (pinfunction "2_2") (pintype "passive"))
      (node (ref "U2") (pin "17") (pinfunction "TXD_17") (pintype "passive"))
    )
    (net (code "60") (name "/U0RXD") (class "Default")
      (node (ref "H2") (pin "6") (pinfunction "6_6") (pintype "passive"))
      (node (ref "R19") (pin "1") (pinfunction "1_1") (pintype "passive"))
      (node (ref "U1") (pin "40") (pinfunction "U0RXD-_GPIO44-_CLK_OUT2_40") (pintype "passive"))
    )
    (net (code "61") (name "/U0TXD") (class "Default")
      (node (ref "H2") (pin "7") (pinfunction "7_7") (pintype "passive"))
      (node (ref "R18") (pin "1") (pinfunction "1_1") (pintype "passive"))
      (node (ref "U1") (pin "39") (pinfunction "U0TXD-_GPIO43-_CLK_OUT1_39") (pintype "passive"))
    )
    (net (code "62") (name "/VBUS_SENSE") (class "Default")
      (node (ref "R11") (pin "2") (pinfunction "2_2") (pintype "passive"))
      (node (ref "R7") (pin "1") (pinfunction "1_1") (pintype "passive"))
      (node (ref "U2") (pin "16") (pinfunction "CBUS3_16") (pintype "passive"))
    )
    (net (code "63") (name "GND") (class "Default")
      (node (ref "C1") (pin "2") (pinfunction "2_2") (pintype "passive"))
      (node (ref "C10") (pin "1") (pinfunction "1_1") (pintype "passive"))
      (node (ref "C11") (pin "1") (pinfunction "1_1") (pintype "passive"))
      (node (ref "C12") (pin "1") (pinfunction "1_1") (pintype "passive"))
      (node (ref "C13") (pin "2") (pinfunction "2_2") (pintype "passive"))
      (node (ref "C14") (pin "1") (pinfunction "1_1") (pintype "passive"))
      (node (ref "C15") (pin "1") (pinfunction "1_1") (pintype "passive"))
      (node (ref "C16") (pin "2") (pinfunction "2_2") (pintype "passive"))
      (node (ref "C17") (pin "1") (pinfunction "1_1") (pintype "passive"))
      (node (ref "C2") (pin "1") (pinfunction "1_1") (pintype "passive"))
      (node (ref "C3") (pin "2") (pinfunction "2_2") (pintype "passive"))
      (node (ref "C4") (pin "2") (pinfunction "2_2") (pintype "passive"))
      (node (ref "C5") (pin "2") (pinfunction "2_2") (pintype "passive"))
      (node (ref "C6") (pin "2") (pinfunction "2_2") (pintype "passive"))
      (node (ref "C7") (pin "2") (pinfunction "2_2") (pintype "passive"))
      (node (ref "C8") (pin "2") (pinfunction "2_2") (pintype "passive"))
      (node (ref "C9") (pin "2") (pinfunction "2_2") (pintype "passive"))
      (node (ref "D2") (pin "2") (pinfunction "2_2") (pintype "passive"))
      (node (ref "D5") (pin "2") (pinfunction "2_2") (pintype "passive"))
      (node (ref "H1") (pin "1") (pinfunction "1_1") (pintype "passive"))
      (node (ref "H1") (pin "23") (pinfunction "23_23") (pintype "passive"))
      (node (ref "H1") (pin "24") (pinfunction "24_24") (pintype "passive"))
      (node (ref "H2") (pin "2") (pinfunction "2_2") (pintype "passive"))
      (node (ref "H2") (pin "24") (pinfunction "24_24") (pintype "passive"))
      (node (ref "J3") (pin "A1B12") (pinfunction "GND_A1B12_A1B12") (pintype "passive"))
      (node (ref "J3") (pin "B1A12") (pinfunction "GND_B1A12_B1A12") (pintype "passive"))
      (node (ref "J3") (pin "S1") (pinfunction "S1_S1") (pintype "passive"))
      (node (ref "J3") (pin "S2") (pinfunction "S2_S2") (pintype "passive"))
      (node (ref "J3") (pin "S3") (pinfunction "S3_S3") (pintype "passive"))
      (node (ref "J3") (pin "S4") (pinfunction "S4_S4") (pintype "passive"))
      (node (ref "J4") (pin "A1B12") (pinfunction "GND_A1B12_A1B12") (pintype "passive"))
      (node (ref "J4") (pin "B1A12") (pinfunction "GND_B1A12_B1A12") (pintype "passive"))
      (node (ref "J4") (pin "S1") (pinfunction "S1_S1") (pintype "passive"))
      (node (ref "J4") (pin "S2") (pinfunction "S2_S2") (pintype "passive"))
      (node (ref "J4") (pin "S3") (pinfunction "S3_S3") (pintype "passive"))
      (node (ref "J4") (pin "S4") (pinfunction "S4_S4") (pintype "passive"))
      (node (ref "L1") (pin "1") (pinfunction "1_1") (pintype "passive"))
      (node (ref "R10") (pin "1") (pinfunction "1_1") (pintype "passive"))
      (node (ref "R11") (pin "1") (pinfunction "1_1") (pintype "passive"))
      (node (ref "R14") (pin "2") (pinfunction "2_2") (pintype "passive"))
      (node (ref "R15") (pin "1") (pinfunction "1_1") (pintype "passive"))
      (node (ref "R8") (pin "2") (pinfunction "2_2") (pintype "passive"))
      (node (ref "R9") (pin "2") (pinfunction "2_2") (pintype "passive"))
      (node (ref "SWT1") (pin "3") (pinfunction "3_3") (pintype "passive"))
      (node (ref "SWT1") (pin "4") (pinfunction "4_4") (pintype "passive"))
      (node (ref "SWT2") (pin "3") (pinfunction "3_3") (pintype "passive"))
      (node (ref "SWT2") (pin "4") (pinfunction "4_4") (pintype "passive"))
      (node (ref "U1") (pin "1") (pinfunction "GND_1_1") (pintype "passive"))
      (node (ref "U1") (pin "2") (pinfunction "GND_2_2") (pintype "passive"))
      (node (ref "U1") (pin "42") (pinfunction "GND_42_42") (pintype "passive"))
      (node (ref "U1") (pin "43") (pinfunction "GND_43_43") (pintype "passive"))
      (node (ref "U1") (pin "46") (pinfunction "GND_46_46") (pintype "passive"))
      (node (ref "U1") (pin "47") (pinfunction "GND_47_47") (pintype "passive"))
      (node (ref "U1") (pin "48") (pinfunction "GND_48_48") (pintype "passive"))
      (node (ref "U1") (pin "49") (pinfunction "GND_49_49") (pintype "passive"))
      (node (ref "U1") (pin "50") (pinfunction "GND_50_50") (pintype "passive"))
      (node (ref "U1") (pin "51") (pinfunction "GND_51_51") (pintype "passive"))
      (node (ref "U1") (pin "52") (pinfunction "GND_52_52") (pintype "passive"))
      (node (ref "U1") (pin "53") (pinfunction "GND_53_53") (pintype "passive"))
      (node (ref "U1") (pin "54") (pinfunction "GND_54_54") (pintype "passive"))
      (node (ref "U1") (pin "55") (pinfunction "GND_55_55") (pintype "passive"))
      (node (ref "U1") (pin "56") (pinfunction "GND_56_56") (pintype "passive"))
      (node (ref "U1") (pin "57") (pinfunction "GND_57_57") (pintype "passive"))
      (node (ref "U1") (pin "58") (pinfunction "GND_58_58") (pintype "passive"))
      (node (ref "U1") (pin "59") (pinfunction "GND_59_59") (pintype "passive"))
      (node (ref "U1") (pin "60") (pinfunction "GND_60_60") (pintype "passive"))
      (node (ref "U1") (pin "61") (pinfunction "GND_61_61") (pintype "passive"))
      (node (ref "U1") (pin "62") (pinfunction "GND_62_62") (pintype "passive"))
      (node (ref "U1") (pin "63") (pinfunction "GND_63_63") (pintype "passive"))
      (node (ref "U1") (pin "64") (pinfunction "GND_64_64") (pintype "passive"))
      (node (ref "U1") (pin "65") (pinfunction "GND_65_65") (pintype "passive"))
      (node (ref "U1") (pin "66") (pinfunction "GND_66_66") (pintype "passive"))
      (node (ref "U1") (pin "67") (pinfunction "GND_67_67") (pintype "passive"))
      (node (ref "U1") (pin "68") (pinfunction "GND_68_68") (pintype "passive"))
      (node (ref "U1") (pin "69") (pinfunction "GND_69_69") (pintype "passive"))
      (node (ref "U1") (pin "70") (pinfunction "GND_70_70") (pintype "passive"))
      (node (ref "U1") (pin "71") (pinfunction "GND_71_71") (pintype "passive"))
      (node (ref "U1") (pin "72") (pinfunction "GND_72_72") (pintype "passive"))
      (node (ref "U1") (pin "73") (pinfunction "GND_73_73") (pintype "passive"))
      (node (ref "U2") (pin "13") (pinfunction "GND_13") (pintype "passive"))
      (node (ref "U2") (pin "21") (pinfunction "GND_21") (pintype "passive"))
      (node (ref "U2") (pin "3") (pinfunction "GND_3") (pintype "passive"))
      (node (ref "U3") (pin "2") (pinfunction "GND_2") (pintype "power_in"))
      (node (ref "U3") (pin "4") (pinfunction "GND_4") (pintype "power_in"))
    )
    (net (code "64") (name "Net-(D1-Pad2)") (class "Default")
      (node (ref "D1") (pin "2") (pinfunction "2_2") (pintype "passive"))
      (node (ref "D3") (pin "2") (pinfunction "2_2") (pintype "passive"))
    )
    (net (code "65") (name "Net-(D4-Pad2)") (class "Default")
      (node (ref "D4") (pin "2") (pinfunction "2_2") (pintype "passive"))
      (node (ref "D6") (pin "2") (pinfunction "2_2") (pintype "passive"))
    )
    (net (code "66") (name "Net-(J3-CC1)") (class "Default")
      (node (ref "J3") (pin "A5") (pinfunction "CC1_A5") (pintype "passive"))
      (node (ref "R10") (pin "2") (pinfunction "2_2") (pintype "passive"))
    )
    (net (code "67") (name "Net-(J3-CC2)") (class "Default")
      (node (ref "J3") (pin "B5") (pinfunction "CC2_B5") (pintype "passive"))
      (node (ref "R9") (pin "1") (pinfunction "1_1") (pintype "passive"))
    )
    (net (code "68") (name "Net-(J4-CC1)") (class "Default")
      (node (ref "J4") (pin "A5") (pinfunction "CC1_A5") (pintype "passive"))
      (node (ref "R15") (pin "2") (pinfunction "2_2") (pintype "passive"))
    )
    (net (code "69") (name "Net-(J4-CC2)") (class "Default")
      (node (ref "J4") (pin "B5") (pinfunction "CC2_B5") (pintype "passive"))
      (node (ref "R14") (pin "1") (pinfunction "1_1") (pintype "passive"))
    )
    (net (code "70") (name "Net-(L1-Pad2)") (class "Default")
      (node (ref "L1") (pin "2") (pinfunction "2_2") (pintype "passive"))
      (node (ref "R12") (pin "1") (pinfunction "1_1") (pintype "passive"))
    )
    (net (code "71") (name "Net-(L2-Pad2)") (class "Default")
      (node (ref "L2") (pin "2") (pinfunction "2_2") (pintype "passive"))
      (node (ref "R13") (pin "1") (pinfunction "1_1") (pintype "passive"))
    )
    (net (code "72") (name "Net-(Q1-B)") (class "Default")
      (node (ref "Q1") (pin "1") (pinfunction "B_1") (pintype "passive"))
      (node (ref "R16") (pin "1") (pinfunction "1_1") (pintype "passive"))
    )
    (net (code "73") (name "Net-(Q2-B)") (class "Default")
      (node (ref "Q2") (pin "1") (pinfunction "B_1") (pintype "passive"))
      (node (ref "R17") (pin "1") (pinfunction "1_1") (pintype "passive"))
    )
    (net (code "74") (name "Net-(U2-CBUS0)") (class "Default")
      (node (ref "R8") (pin "1") (pinfunction "1_1") (pintype "passive"))
      (node (ref "U2") (pin "15") (pinfunction "CBUS0_15") (pintype "passive"))
    )
    (net (code "75") (name "Net-(U2-~{RESET})") (class "Default")
      (node (ref "C7") (pin "1") (pinfunction "1_1") (pintype "passive"))
      (node (ref "R6") (pin "2") (pinfunction "2_2") (pintype "passive"))
      (node (ref "U2") (pin "11") (pinfunction "~{RESET}_11") (pintype "passive"))
    )
    (net (code "76") (name "unconnected-(J3-SBU1-PadA8)") (class "Default")
      (node (ref "J3") (pin "A8") (pinfunction "SBU1_A8") (pintype "passive+no_connect"))
    )
    (net (code "77") (name "unconnected-(J3-SBU2-PadB8)") (class "Default")
      (node (ref "J3") (pin "B8") (pinfunction "SBU2_B8") (pintype "passive+no_connect"))
    )
    (net (code "78") (name "unconnected-(J4-SBU1-PadA8)") (class "Default")
      (node (ref "J4") (pin "A8") (pinfunction "SBU1_A8") (pintype "passive+no_connect"))
    )
    (net (code "79") (name "unconnected-(J4-SBU2-PadB8)") (class "Default")
      (node (ref "J4") (pin "B8") (pinfunction "SBU2_B8") (pintype "passive+no_connect"))
    )
    (net (code "80") (name "unconnected-(U2-CBUS1-Pad14)") (class "Default")
      (node (ref "U2") (pin "14") (pinfunction "CBUS1_14") (pintype "passive+no_connect"))
    )
    (net (code "81") (name "unconnected-(U2-CBUS2-Pad7)") (class "Default")
      (node (ref "U2") (pin "7") (pinfunction "CBUS2_7") (pintype "passive+no_connect"))
    )
    (net (code "82") (name "unconnected-(U2-~{CTS}-Pad6)") (class "Default")
      (node (ref "U2") (pin "6") (pinfunction "~{CTS}_6") (pintype "passive+no_connect"))
    )
    (net (code "83") (name "unconnected-(U2-~{DCD}-Pad5)") (class "Default")
      (node (ref "U2") (pin "5") (pinfunction "~{DCD}_5") (pintype "passive+no_connect"))
    )
    (net (code "84") (name "unconnected-(U2-~{DSR}-Pad4)") (class "Default")
      (node (ref "U2") (pin "4") (pinfunction "~{DSR}_4") (pintype "passive+no_connect"))
    )
    (net (code "85") (name "unconnected-(U2-~{RI}-Pad2)") (class "Default")
      (node (ref "U2") (pin "2") (pinfunction "~{RI}_2") (pintype "passive+no_connect"))
    )
  )
)
